# basic_attiny84.net
KiCad netlist of a schematic drawn in EAGLE
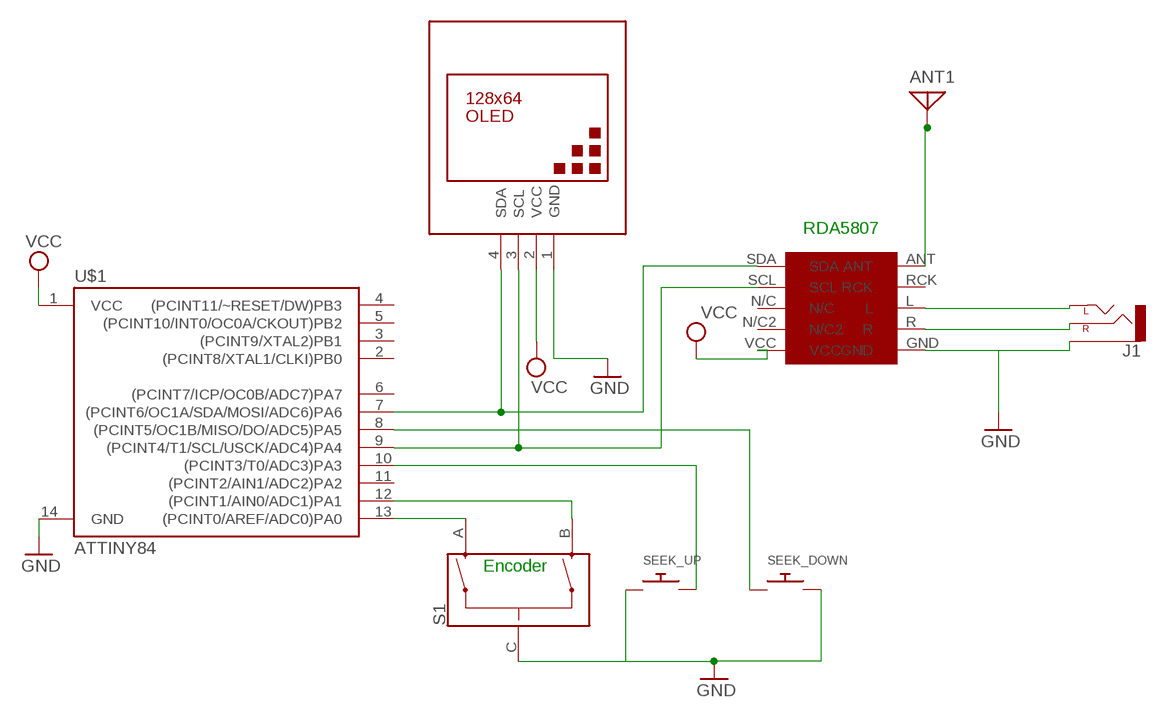
[diagram p0: schematic, sheet 1]

(export (version "E")
  (design (tool "Eeschema 10.0.6"))
  (components
    (comp (ref "ANT1")
      (value "ANTENNA")
      (footprint "eagle-import:PAD-01")
      (libsource (lib "eagle-import") (part "ANTENNA"))
    )
    (comp (ref "J1")
      (value "AUDIO_JACK_2.5MMSPECIAL_POGO_PINS")
      (footprint "eagle-import:STEREOJACK2.5MM_SPECIAL_POGOPINS")
      (libsource (lib "eagle-import") (part "AUDIO_JACK_2.5MMSPECIAL_POGO_PINS"))
    )
    (comp (ref "S1")
      (value "ENCODER")
      (footprint "eagle-import:ENCODER-16MM-QUAD")
      (libsource (lib "eagle-import") (part "ENCODER"))
    )
    (comp (ref "SEEK_DOWN")
      (value "SWITCH_PUSHBUTTONC&K_KSS")
      (footprint "eagle-import:BTN_CK_KSS")
      (libsource (lib "eagle-import") (part "SWITCH_PUSHBUTTONC&K_KSS"))
    )
    (comp (ref "SEEK_UP")
      (value "SWITCH_PUSHBUTTONC&K_KSS")
      (footprint "eagle-import:BTN_CK_KSS")
      (libsource (lib "eagle-import") (part "SWITCH_PUSHBUTTONC&K_KSS"))
    )
    (comp (ref "U$1")
      (value "ATTINY84")
      (footprint "eagle-import:SO14")
      (libsource (lib "eagle-import") (part "ATTINY84"))
    )
    (comp (ref "U$2")
      (value "RDA")
      (footprint "eagle-import:RDA")
      (libsource (lib "eagle-import") (part "RDA"))
    )
    (comp (ref "U$3")
      (value "DISPLAY-OLED-128X64-I2C")
      (footprint "eagle-import:DISPLAY-OLED-128X64-I2C")
      (libsource (lib "eagle-import") (part "DISPLAY-OLED-128X64-I2C"))
    )
  )
  (nets
    (net (code "1") (name "GND") (class "Default")
      (node (ref "J1") (pin "RING1") (pinfunction "SLEEVE_RING1") (pintype "bidirectional"))
      (node (ref "S1") (pin "C") (pinfunction "C_C") (pintype "bidirectional"))
      (node (ref "SEEK_DOWN") (pin "P$2") (pinfunction "P$2_P$2") (pintype "passive"))
      (node (ref "SEEK_UP") (pin "P$1") (pinfunction "P$1_P$1") (pintype "passive"))
      (node (ref "U$1") (pin "14") (pinfunction "GND_14") (pintype "bidirectional"))
      (node (ref "U$2") (pin "GND") (pinfunction "GND_GND") (pintype "power_in"))
      (node (ref "U$3") (pin "1") (pinfunction "GND_1") (pintype "power_in"))
    )
    (net (code "2") (name "Net-(ANT1-Pad1)") (class "Default")
      (node (ref "ANT1") (pin "1") (pinfunction "1_1") (pintype "output"))
      (node (ref "U$2") (pin "ANT") (pinfunction "ANT_ANT") (pintype "input"))
    )
    (net (code "3") (name "Net-(J1-LEFT)") (class "Default")
      (node (ref "J1") (pin "SHIELD") (pinfunction "LEFT_SHIELD") (pintype "bidirectional"))
      (node (ref "U$2") (pin "L") (pinfunction "L_L") (pintype "output"))
    )
    (net (code "4") (name "Net-(J1-RIGHT)") (class "Default")
      (node (ref "J1") (pin "TIP") (pinfunction "RIGHT_TIP") (pintype "bidirectional"))
      (node (ref "U$2") (pin "R") (pinfunction "R_R") (pintype "output"))
    )
    (net (code "5") (name "Net-(U$1-(PCINT0{slash}AREF{slash}ADC0)PA0)") (class "Default")
      (node (ref "S1") (pin "A") (pinfunction "A_A") (pintype "bidirectional"))
      (node (ref "U$1") (pin "13") (pinfunction "(PCINT0/AREF/ADC0)PA0_13") (pintype "bidirectional"))
    )
    (net (code "6") (name "Net-(U$1-(PCINT1{slash}AIN0{slash}ADC1)PA1)") (class "Default")
      (node (ref "S1") (pin "B") (pinfunction "B_B") (pintype "bidirectional"))
      (node (ref "U$1") (pin "12") (pinfunction "(PCINT1/AIN0/ADC1)PA1_12") (pintype "bidirectional"))
    )
    (net (code "7") (name "Net-(U$1-(PCINT3{slash}T0{slash}ADC3)PA3)") (class "Default")
      (node (ref "SEEK_UP") (pin "P$2") (pinfunction "P$2_P$2") (pintype "passive"))
      (node (ref "U$1") (pin "10") (pinfunction "(PCINT3/T0/ADC3)PA3_10") (pintype "bidirectional"))
    )
    (net (code "8") (name "Net-(U$1-(PCINT4{slash}T1{slash}SCL{slash}USCK{slash}ADC4)PA4)") (class "Default")
      (node (ref "U$1") (pin "9") (pinfunction "(PCINT4/T1/SCL/USCK/ADC4)PA4_9") (pintype "bidirectional"))
      (node (ref "U$2") (pin "SCL") (pinfunction "SCL_SCL") (pintype "bidirectional"))
      (node (ref "U$3") (pin "3") (pinfunction "SCL_3") (pintype "bidirectional"))
    )
    (net (code "9") (name "Net-(U$1-(PCINT5{slash}OC1B{slash}MISO{slash}DO{slash}ADC5)PA5)") (class "Default")
      (node (ref "SEEK_DOWN") (pin "P$1") (pinfunction "P$1_P$1") (pintype "passive"))
      (node (ref "U$1") (pin "8") (pinfunction "(PCINT5/OC1B/MISO/DO/ADC5)PA5_8") (pintype "bidirectional"))
    )
    (net (code "10") (name "Net-(U$1-(PCINT6{slash}OC1A{slash}SDA{slash}MOSI{slash}ADC6)PA6)") (class "Default")
      (node (ref "U$1") (pin "7") (pinfunction "(PCINT6/OC1A/SDA/MOSI/ADC6)PA6_7") (pintype "bidirectional"))
      (node (ref "U$2") (pin "SDA") (pinfunction "SDA_SDA") (pintype "bidirectional"))
      (node (ref "U$3") (pin "4") (pinfunction "SDA_4") (pintype "bidirectional"))
    )
    (net (code "11") (name "VCC") (class "Default")
      (node (ref "U$1") (pin "1") (pinfunction "VCC_1") (pintype "bidirectional"))
      (node (ref "U$2") (pin "VCC") (pinfunction "VCC_VCC") (pintype "power_in"))
      (node (ref "U$3") (pin "2") (pinfunction "VCC_2") (pintype "power_in"))
    )
    (net (code "12") (name "unconnected-(U$1-(PCINT2{slash}AIN1{slash}ADC2)PA2-Pad11)") (class "Default")
      (node (ref "U$1") (pin "11") (pinfunction "(PCINT2/AIN1/ADC2)PA2_11") (pintype "bidirectional"))
    )
    (net (code "13") (name "unconnected-(U$1-(PCINT7{slash}ICP{slash}OC0B{slash}ADC7)PA7-Pad6)") (class "Default")
      (node (ref "U$1") (pin "6") (pinfunction "(PCINT7/ICP/OC0B/ADC7)PA7_6") (pintype "bidirectional"))
    )
    (net (code "14") (name "unconnected-(U$1-(PCINT8{slash}XTAL1{slash}CLKI)PB0-Pad2)") (class "Default")
      (node (ref "U$1") (pin "2") (pinfunction "(PCINT8/XTAL1/CLKI)PB0_2") (pintype "bidirectional"))
    )
    (net (code "15") (name "unconnected-(U$1-(PCINT9{slash}XTAL2)PB1-Pad3)") (class "Default")
      (node (ref "U$1") (pin "3") (pinfunction "(PCINT9/XTAL2)PB1_3") (pintype "bidirectional"))
    )
    (net (code "16") (name "unconnected-(U$1-(PCINT10{slash}INT0{slash}OC0A{slash}CKOUT)PB2-Pad5)") (class "Default")
      (node (ref "U$1") (pin "5") (pinfunction "(PCINT10/INT0/OC0A/CKOUT)PB2_5") (pintype "bidirectional"))
    )
    (net (code "17") (name "unconnected-(U$1-(PCINT11{slash}~{RESET{slash}DW})PB3-Pad4)") (class "Default")
      (node (ref "U$1") (pin "4") (pinfunction "(PCINT11/~{RESET/DW})PB3_4") (pintype "bidirectional"))
    )
    (net (code "18") (name "unconnected-(U$2-PadN{slash}C)") (class "Default")
      (node (ref "U$2") (pin "N/C") (pinfunction "N/C_N/C") (pintype "passive"))
    )
    (net (code "19") (name "unconnected-(U$2-PadN{slash}C2)") (class "Default")
      (node (ref "U$2") (pin "N/C2") (pinfunction "N/C2_N/C2") (pintype "passive"))
    )
    (net (code "20") (name "unconnected-(U$2-PadRCK)") (class "Default")
      (node (ref "U$2") (pin "RCK") (pinfunction "RCK_RCK") (pintype "bidirectional"))
    )
  )
)
